# AudioUSB.net
KiCad netlist of a schematic drawn in EAGLE
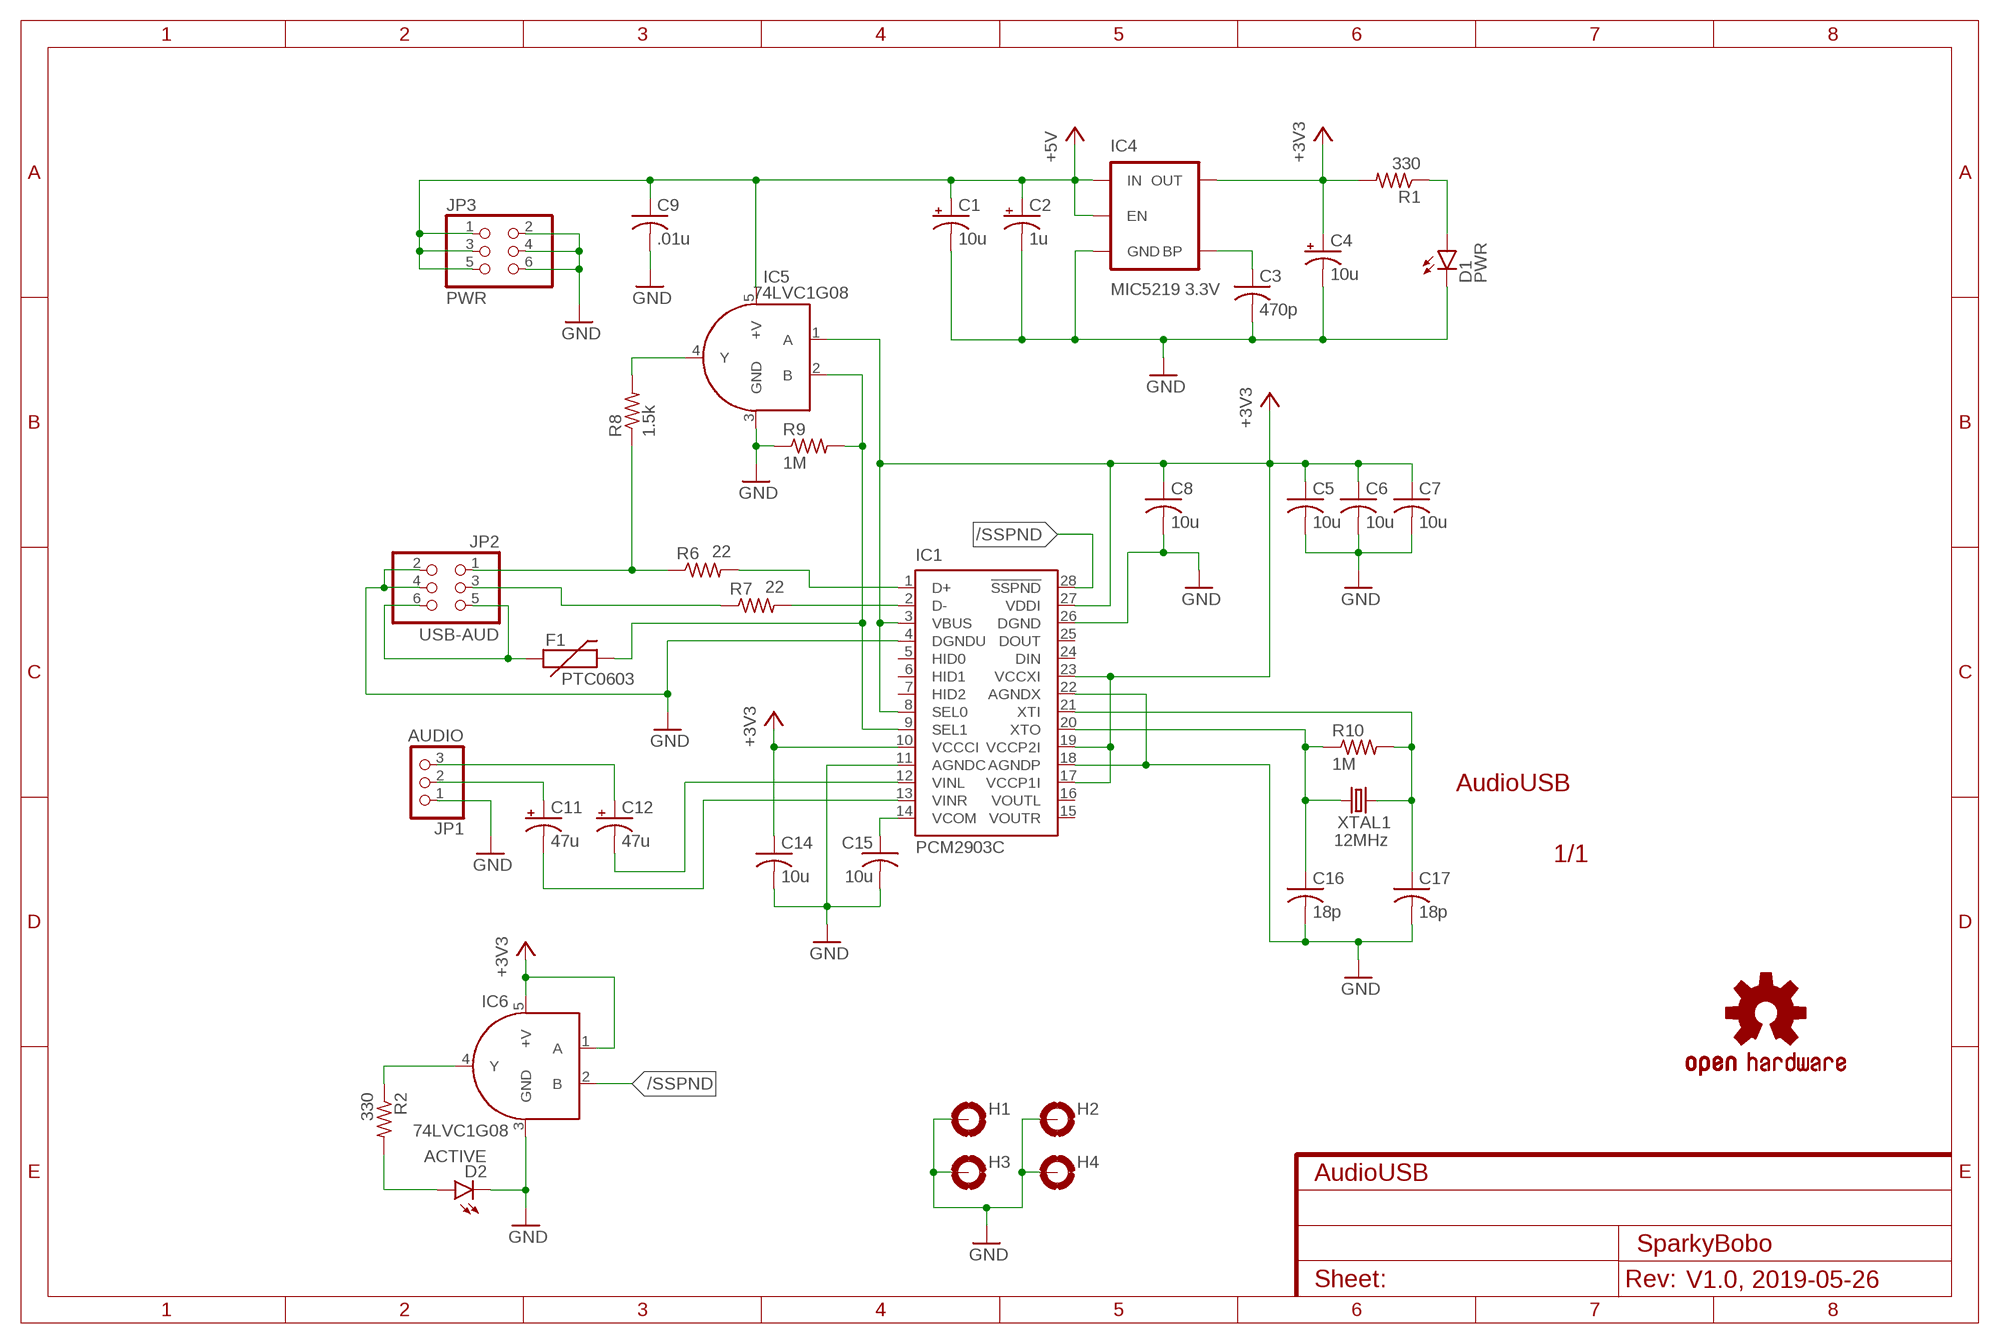
[diagram p0: schematic, sheet 1]

(export (version "E")
  (design (tool "Eeschema 10.0.6"))
  (components
    (comp (ref "C1")
      (value "10u")
      (footprint "eagle-import:PANASONIC_B")
      (libsource (lib "eagle-import") (part "CPOL-USB"))
    )
    (comp (ref "C2")
      (value "1u")
      (footprint "eagle-import:PANASONIC_B")
      (libsource (lib "eagle-import") (part "CPOL-USB"))
    )
    (comp (ref "C3")
      (value "470p")
      (footprint "eagle-import:C0603")
      (libsource (lib "eagle-import") (part "C-USC0603"))
    )
    (comp (ref "C4")
      (value "10u")
      (footprint "eagle-import:PANASONIC_B")
      (libsource (lib "eagle-import") (part "CPOL-USB"))
    )
    (comp (ref "C5")
      (value "10u")
      (footprint "eagle-import:C0603")
      (libsource (lib "eagle-import") (part "C-USC0603"))
    )
    (comp (ref "C6")
      (value "10u")
      (footprint "eagle-import:C0603")
      (libsource (lib "eagle-import") (part "C-USC0603"))
    )
    (comp (ref "C7")
      (value "10u")
      (footprint "eagle-import:C0603")
      (libsource (lib "eagle-import") (part "C-USC0603"))
    )
    (comp (ref "C8")
      (value "10u")
      (footprint "eagle-import:C0603")
      (libsource (lib "eagle-import") (part "C-USC0603"))
    )
    (comp (ref "C9")
      (value ".01u")
      (footprint "eagle-import:C0603")
      (libsource (lib "eagle-import") (part "C-USC0603"))
    )
    (comp (ref "C11")
      (value "47u")
      (footprint "eagle-import:PANASONIC_D")
      (libsource (lib "eagle-import") (part "CPOL-USD"))
    )
    (comp (ref "C12")
      (value "47u")
      (footprint "eagle-import:PANASONIC_D")
      (libsource (lib "eagle-import") (part "CPOL-USD"))
    )
    (comp (ref "C14")
      (value "10u")
      (footprint "eagle-import:C0603")
      (libsource (lib "eagle-import") (part "C-USC0603"))
    )
    (comp (ref "C15")
      (value "10u")
      (footprint "eagle-import:C0603")
      (libsource (lib "eagle-import") (part "C-USC0603"))
    )
    (comp (ref "C16")
      (value "18p")
      (footprint "eagle-import:C0603")
      (libsource (lib "eagle-import") (part "C-USC0603"))
    )
    (comp (ref "C17")
      (value "18p")
      (footprint "eagle-import:C0603")
      (libsource (lib "eagle-import") (part "C-USC0603"))
    )
    (comp (ref "D1")
      (value "PWR")
      (footprint "eagle-import:LED-0603")
      (libsource (lib "eagle-import") (part "LED0603"))
    )
    (comp (ref "D2")
      (value "ACTIVE")
      (footprint "eagle-import:LED-0603")
      (libsource (lib "eagle-import") (part "LED0603"))
    )
    (comp (ref "F1")
      (value "PTC0603")
      (footprint "eagle-import:0603")
      (libsource (lib "eagle-import") (part "PTC0603"))
    )
    (comp (ref "H1")
      (value "MOUNT-PAD-ROUND2.8")
      (footprint "eagle-import:2,8-PAD")
      (libsource (lib "eagle-import") (part "MOUNT-PAD-ROUND2.8"))
    )
    (comp (ref "H2")
      (value "MOUNT-PAD-ROUND2.8")
      (footprint "eagle-import:2,8-PAD")
      (libsource (lib "eagle-import") (part "MOUNT-PAD-ROUND2.8"))
    )
    (comp (ref "H3")
      (value "MOUNT-PAD-ROUND2.8")
      (footprint "eagle-import:2,8-PAD")
      (libsource (lib "eagle-import") (part "MOUNT-PAD-ROUND2.8"))
    )
    (comp (ref "H4")
      (value "MOUNT-PAD-ROUND2.8")
      (footprint "eagle-import:2,8-PAD")
      (libsource (lib "eagle-import") (part "MOUNT-PAD-ROUND2.8"))
    )
    (comp (ref "IC1")
      (value "PCM2903C")
      (footprint "eagle-import:SSOP28")
      (libsource (lib "eagle-import") (part "PCM2903C"))
    )
    (comp (ref "IC4")
      (value "MIC5219 3.3V")
      (footprint "eagle-import:SOT23-5")
      (libsource (lib "eagle-import") (part "V_REG_MIC52193.3V"))
    )
    (comp (ref "IC5")
      (value "74LVC1G08")
      (footprint "eagle-import:SOT23-5")
      (libsource (lib "eagle-import") (part "SN74LVC1G08"))
    )
    (comp (ref "IC6")
      (value "74LVC1G08")
      (footprint "eagle-import:SOT23-5")
      (libsource (lib "eagle-import") (part "SN74LVC1G08"))
    )
    (comp (ref "JP1")
      (value "AUDIO")
      (footprint "eagle-import:1X03")
      (libsource (lib "eagle-import") (part "PINHD-1X3"))
    )
    (comp (ref "JP2")
      (value "USB-AUD")
      (footprint "eagle-import:2X03")
      (libsource (lib "eagle-import") (part "PINHD-2X3"))
    )
    (comp (ref "JP3")
      (value "PWR")
      (footprint "eagle-import:2X03")
      (libsource (lib "eagle-import") (part "PINHD-2X3"))
    )
    (comp (ref "LOGO1")
      (value "OSHW-LOGOS")
      (footprint "eagle-import:OSHW-LOGO-S")
      (libsource (lib "eagle-import") (part "OSHW-LOGOS"))
    )
    (comp (ref "R1")
      (value "330")
      (footprint "eagle-import:R0603")
      (libsource (lib "eagle-import") (part "R-US_R0603"))
    )
    (comp (ref "R2")
      (value "330")
      (footprint "eagle-import:R0603")
      (libsource (lib "eagle-import") (part "R-US_R0603"))
    )
    (comp (ref "R6")
      (value "22")
      (footprint "eagle-import:R0603")
      (libsource (lib "eagle-import") (part "R-US_R0603"))
    )
    (comp (ref "R7")
      (value "22")
      (footprint "eagle-import:R0603")
      (libsource (lib "eagle-import") (part "R-US_R0603"))
    )
    (comp (ref "R8")
      (value "1.5k")
      (footprint "eagle-import:R0603")
      (libsource (lib "eagle-import") (part "R-US_R0603"))
    )
    (comp (ref "R9")
      (value "1M")
      (footprint "eagle-import:R0603")
      (libsource (lib "eagle-import") (part "R-US_R0603"))
    )
    (comp (ref "R10")
      (value "1M")
      (footprint "eagle-import:R0603")
      (libsource (lib "eagle-import") (part "R-US_R0603"))
    )
    (comp (ref "XTAL1")
      (value "12MHz")
      (footprint "eagle-import:HC49US")
      (libsource (lib "eagle-import") (part "CRYSTALHC49US"))
    )
  )
  (nets
    (net (code "1") (name "+3V3") (class "Default")
      (node (ref "C14") (pin "1") (pinfunction "1_1") (pintype "passive"))
      (node (ref "C4") (pin "+") (pinfunction "+_+") (pintype "passive"))
      (node (ref "C5") (pin "1") (pinfunction "1_1") (pintype "passive"))
      (node (ref "C6") (pin "1") (pinfunction "1_1") (pintype "passive"))
      (node (ref "C7") (pin "1") (pinfunction "1_1") (pintype "passive"))
      (node (ref "C8") (pin "1") (pinfunction "1_1") (pintype "passive"))
      (node (ref "IC1") (pin "10") (pinfunction "VCCCI_10") (pintype "power_in"))
      (node (ref "IC1") (pin "17") (pinfunction "VCCP1I_17") (pintype "input"))
      (node (ref "IC1") (pin "19") (pinfunction "VCCP2I_19") (pintype "power_in"))
      (node (ref "IC1") (pin "23") (pinfunction "VCCXI_23") (pintype "power_in"))
      (node (ref "IC1") (pin "27") (pinfunction "VDDI_27") (pintype "power_in"))
      (node (ref "IC1") (pin "3") (pinfunction "VBUS_3") (pintype "power_in"))
      (node (ref "IC1") (pin "8") (pinfunction "SEL0_8") (pintype "input"))
      (node (ref "IC4") (pin "5") (pinfunction "OUT_5") (pintype "passive"))
      (node (ref "IC5") (pin "1") (pinfunction "A_1") (pintype "input"))
      (node (ref "IC6") (pin "1") (pinfunction "A_1") (pintype "input"))
      (node (ref "IC6") (pin "5") (pinfunction "+V_5") (pintype "power_in"))
      (node (ref "R1") (pin "2") (pinfunction "2_2") (pintype "passive"))
    )
    (net (code "2") (name "+5V") (class "Default")
      (node (ref "C1") (pin "+") (pinfunction "+_+") (pintype "passive"))
      (node (ref "C2") (pin "+") (pinfunction "+_+") (pintype "passive"))
      (node (ref "C9") (pin "1") (pinfunction "1_1") (pintype "passive"))
      (node (ref "IC4") (pin "1") (pinfunction "IN_1") (pintype "input"))
      (node (ref "IC4") (pin "3") (pinfunction "EN_3") (pintype "input"))
      (node (ref "IC5") (pin "5") (pinfunction "+V_5") (pintype "power_in"))
      (node (ref "JP3") (pin "1") (pinfunction "1_1") (pintype "passive"))
      (node (ref "JP3") (pin "3") (pinfunction "3_3") (pintype "passive"))
      (node (ref "JP3") (pin "5") (pinfunction "5_5") (pintype "passive"))
    )
    (net (code "3") (name "GND") (class "Default")
      (node (ref "C1") (pin "-") (pinfunction "-_-") (pintype "passive"))
      (node (ref "C14") (pin "2") (pinfunction "2_2") (pintype "passive"))
      (node (ref "C15") (pin "2") (pinfunction "2_2") (pintype "passive"))
      (node (ref "C16") (pin "2") (pinfunction "2_2") (pintype "passive"))
      (node (ref "C17") (pin "2") (pinfunction "2_2") (pintype "passive"))
      (node (ref "C2") (pin "-") (pinfunction "-_-") (pintype "passive"))
      (node (ref "C3") (pin "2") (pinfunction "2_2") (pintype "passive"))
      (node (ref "C4") (pin "-") (pinfunction "-_-") (pintype "passive"))
      (node (ref "C5") (pin "2") (pinfunction "2_2") (pintype "passive"))
      (node (ref "C6") (pin "2") (pinfunction "2_2") (pintype "passive"))
      (node (ref "C7") (pin "2") (pinfunction "2_2") (pintype "passive"))
      (node (ref "C8") (pin "2") (pinfunction "2_2") (pintype "passive"))
      (node (ref "C9") (pin "2") (pinfunction "2_2") (pintype "passive"))
      (node (ref "D1") (pin "C") (pinfunction "C_C") (pintype "passive"))
      (node (ref "D2") (pin "C") (pinfunction "C_C") (pintype "passive"))
      (node (ref "H1") (pin "B2,8") (pinfunction "MOUNT_B2,8") (pintype "passive"))
      (node (ref "H2") (pin "B2,8") (pinfunction "MOUNT_B2,8") (pintype "passive"))
      (node (ref "H3") (pin "B2,8") (pinfunction "MOUNT_B2,8") (pintype "passive"))
      (node (ref "H4") (pin "B2,8") (pinfunction "MOUNT_B2,8") (pintype "passive"))
      (node (ref "IC1") (pin "11") (pinfunction "AGNDC_11") (pintype "power_in"))
      (node (ref "IC1") (pin "18") (pinfunction "AGNDP_18") (pintype "power_in"))
      (node (ref "IC1") (pin "22") (pinfunction "AGNDX_22") (pintype "power_in"))
      (node (ref "IC1") (pin "26") (pinfunction "DGND_26") (pintype "power_in"))
      (node (ref "IC1") (pin "4") (pinfunction "DGNDU_4") (pintype "power_in"))
      (node (ref "IC4") (pin "2") (pinfunction "GND_2") (pintype "input"))
      (node (ref "IC5") (pin "3") (pinfunction "GND_3") (pintype "power_in"))
      (node (ref "IC6") (pin "3") (pinfunction "GND_3") (pintype "power_in"))
      (node (ref "JP1") (pin "1") (pinfunction "1_1") (pintype "passive"))
      (node (ref "JP2") (pin "2") (pinfunction "2_2") (pintype "passive"))
      (node (ref "JP2") (pin "4") (pinfunction "4_4") (pintype "passive"))
      (node (ref "JP3") (pin "2") (pinfunction "2_2") (pintype "passive"))
      (node (ref "JP3") (pin "4") (pinfunction "4_4") (pintype "passive"))
      (node (ref "JP3") (pin "6") (pinfunction "6_6") (pintype "passive"))
      (node (ref "R9") (pin "1") (pinfunction "1_1") (pintype "passive"))
    )
    (net (code "4") (name "Net-(C11-Pad+)") (class "Default")
      (node (ref "C11") (pin "+") (pinfunction "+_+") (pintype "passive"))
      (node (ref "JP1") (pin "2") (pinfunction "2_2") (pintype "passive"))
    )
    (net (code "5") (name "Net-(C12-Pad+)") (class "Default")
      (node (ref "C12") (pin "+") (pinfunction "+_+") (pintype "passive"))
      (node (ref "JP1") (pin "3") (pinfunction "3_3") (pintype "passive"))
    )
    (net (code "6") (name "Net-(D1-PadA)") (class "Default")
      (node (ref "D1") (pin "A") (pinfunction "A_A") (pintype "passive"))
      (node (ref "R1") (pin "1") (pinfunction "1_1") (pintype "passive"))
    )
    (net (code "7") (name "Net-(D2-PadA)") (class "Default")
      (node (ref "D2") (pin "A") (pinfunction "A_A") (pintype "passive"))
      (node (ref "R2") (pin "2") (pinfunction "2_2") (pintype "passive"))
    )
    (net (code "8") (name "Net-(F1-Pad1)") (class "Default")
      (node (ref "F1") (pin "1") (pinfunction "1_1") (pintype "bidirectional"))
      (node (ref "JP2") (pin "5") (pinfunction "5_5") (pintype "passive"))
      (node (ref "JP2") (pin "6") (pinfunction "6_6") (pintype "passive"))
    )
    (net (code "9") (name "Net-(IC1-D+)") (class "Default")
      (node (ref "IC1") (pin "1") (pinfunction "D+_1") (pintype "bidirectional"))
      (node (ref "R6") (pin "2") (pinfunction "2_2") (pintype "passive"))
    )
    (net (code "10") (name "Net-(IC1-D-)") (class "Default")
      (node (ref "IC1") (pin "2") (pinfunction "D-_2") (pintype "bidirectional"))
      (node (ref "R7") (pin "2") (pinfunction "2_2") (pintype "passive"))
    )
    (net (code "11") (name "Net-(IC1-SEL1)") (class "Default")
      (node (ref "F1") (pin "2") (pinfunction "2_2") (pintype "bidirectional"))
      (node (ref "IC1") (pin "9") (pinfunction "SEL1_9") (pintype "input"))
      (node (ref "IC5") (pin "2") (pinfunction "B_2") (pintype "input"))
      (node (ref "R9") (pin "2") (pinfunction "2_2") (pintype "passive"))
    )
    (net (code "12") (name "Net-(IC1-VCOM)") (class "Default")
      (node (ref "C15") (pin "1") (pinfunction "1_1") (pintype "passive"))
      (node (ref "IC1") (pin "14") (pinfunction "VCOM_14") (pintype "power_in"))
    )
    (net (code "13") (name "Net-(IC1-VINL)") (class "Default")
      (node (ref "C12") (pin "-") (pinfunction "-_-") (pintype "passive"))
      (node (ref "IC1") (pin "12") (pinfunction "VINL_12") (pintype "input"))
    )
    (net (code "14") (name "Net-(IC1-VINR)") (class "Default")
      (node (ref "C11") (pin "-") (pinfunction "-_-") (pintype "passive"))
      (node (ref "IC1") (pin "13") (pinfunction "VINR_13") (pintype "input"))
    )
    (net (code "15") (name "Net-(IC1-XTI)") (class "Default")
      (node (ref "C17") (pin "1") (pinfunction "1_1") (pintype "passive"))
      (node (ref "IC1") (pin "21") (pinfunction "XTI_21") (pintype "input"))
      (node (ref "R10") (pin "2") (pinfunction "2_2") (pintype "passive"))
      (node (ref "XTAL1") (pin "2") (pinfunction "2_2") (pintype "passive"))
    )
    (net (code "16") (name "Net-(IC1-XTO)") (class "Default")
      (node (ref "C16") (pin "1") (pinfunction "1_1") (pintype "passive"))
      (node (ref "IC1") (pin "20") (pinfunction "XTO_20") (pintype "output"))
      (node (ref "R10") (pin "1") (pinfunction "1_1") (pintype "passive"))
      (node (ref "XTAL1") (pin "1") (pinfunction "1_1") (pintype "passive"))
    )
    (net (code "17") (name "Net-(IC4-BP)") (class "Default")
      (node (ref "C3") (pin "1") (pinfunction "1_1") (pintype "passive"))
      (node (ref "IC4") (pin "4") (pinfunction "BP_4") (pintype "input"))
    )
    (net (code "18") (name "Net-(IC5-Y)") (class "Default")
      (node (ref "IC5") (pin "4") (pinfunction "Y_4") (pintype "output"))
      (node (ref "R8") (pin "2") (pinfunction "2_2") (pintype "passive"))
    )
    (net (code "19") (name "Net-(IC6-Y)") (class "Default")
      (node (ref "IC6") (pin "4") (pinfunction "Y_4") (pintype "output"))
      (node (ref "R2") (pin "1") (pinfunction "1_1") (pintype "passive"))
    )
    (net (code "20") (name "Net-(JP2-Pad1)") (class "Default")
      (node (ref "JP2") (pin "1") (pinfunction "1_1") (pintype "passive"))
      (node (ref "R6") (pin "1") (pinfunction "1_1") (pintype "passive"))
      (node (ref "R8") (pin "1") (pinfunction "1_1") (pintype "passive"))
    )
    (net (code "21") (name "Net-(JP2-Pad3)") (class "Default")
      (node (ref "JP2") (pin "3") (pinfunction "3_3") (pintype "passive"))
      (node (ref "R7") (pin "1") (pinfunction "1_1") (pintype "passive"))
    )
    (net (code "22") (name "unconnected-(IC1-DIN-Pad24)") (class "Default")
      (node (ref "IC1") (pin "24") (pinfunction "DIN_24") (pintype "input"))
    )
    (net (code "23") (name "unconnected-(IC1-DOUT-Pad25)") (class "Default")
      (node (ref "IC1") (pin "25") (pinfunction "DOUT_25") (pintype "output"))
    )
    (net (code "24") (name "unconnected-(IC1-HID0-Pad5)") (class "Default")
      (node (ref "IC1") (pin "5") (pinfunction "HID0_5") (pintype "input"))
    )
    (net (code "25") (name "unconnected-(IC1-HID1-Pad6)") (class "Default")
      (node (ref "IC1") (pin "6") (pinfunction "HID1_6") (pintype "input"))
    )
    (net (code "26") (name "unconnected-(IC1-HID2-Pad7)") (class "Default")
      (node (ref "IC1") (pin "7") (pinfunction "HID2_7") (pintype "input"))
    )
    (net (code "27") (name "unconnected-(IC1-VOUTL-Pad16)") (class "Default")
      (node (ref "IC1") (pin "16") (pinfunction "VOUTL_16") (pintype "output"))
    )
    (net (code "28") (name "unconnected-(IC1-VOUTR-Pad15)") (class "Default")
      (node (ref "IC1") (pin "15") (pinfunction "VOUTR_15") (pintype "output"))
    )
    (net (code "29") (name "{slash}SSPND") (class "Default")
      (node (ref "IC1") (pin "28") (pinfunction "~{SSPND}_28") (pintype "output"))
      (node (ref "IC6") (pin "2") (pinfunction "B_2") (pintype "input"))
    )
  )
)
